# m140_attiny_V5c.net
KiCad netlist of a schematic drawn in EAGLE
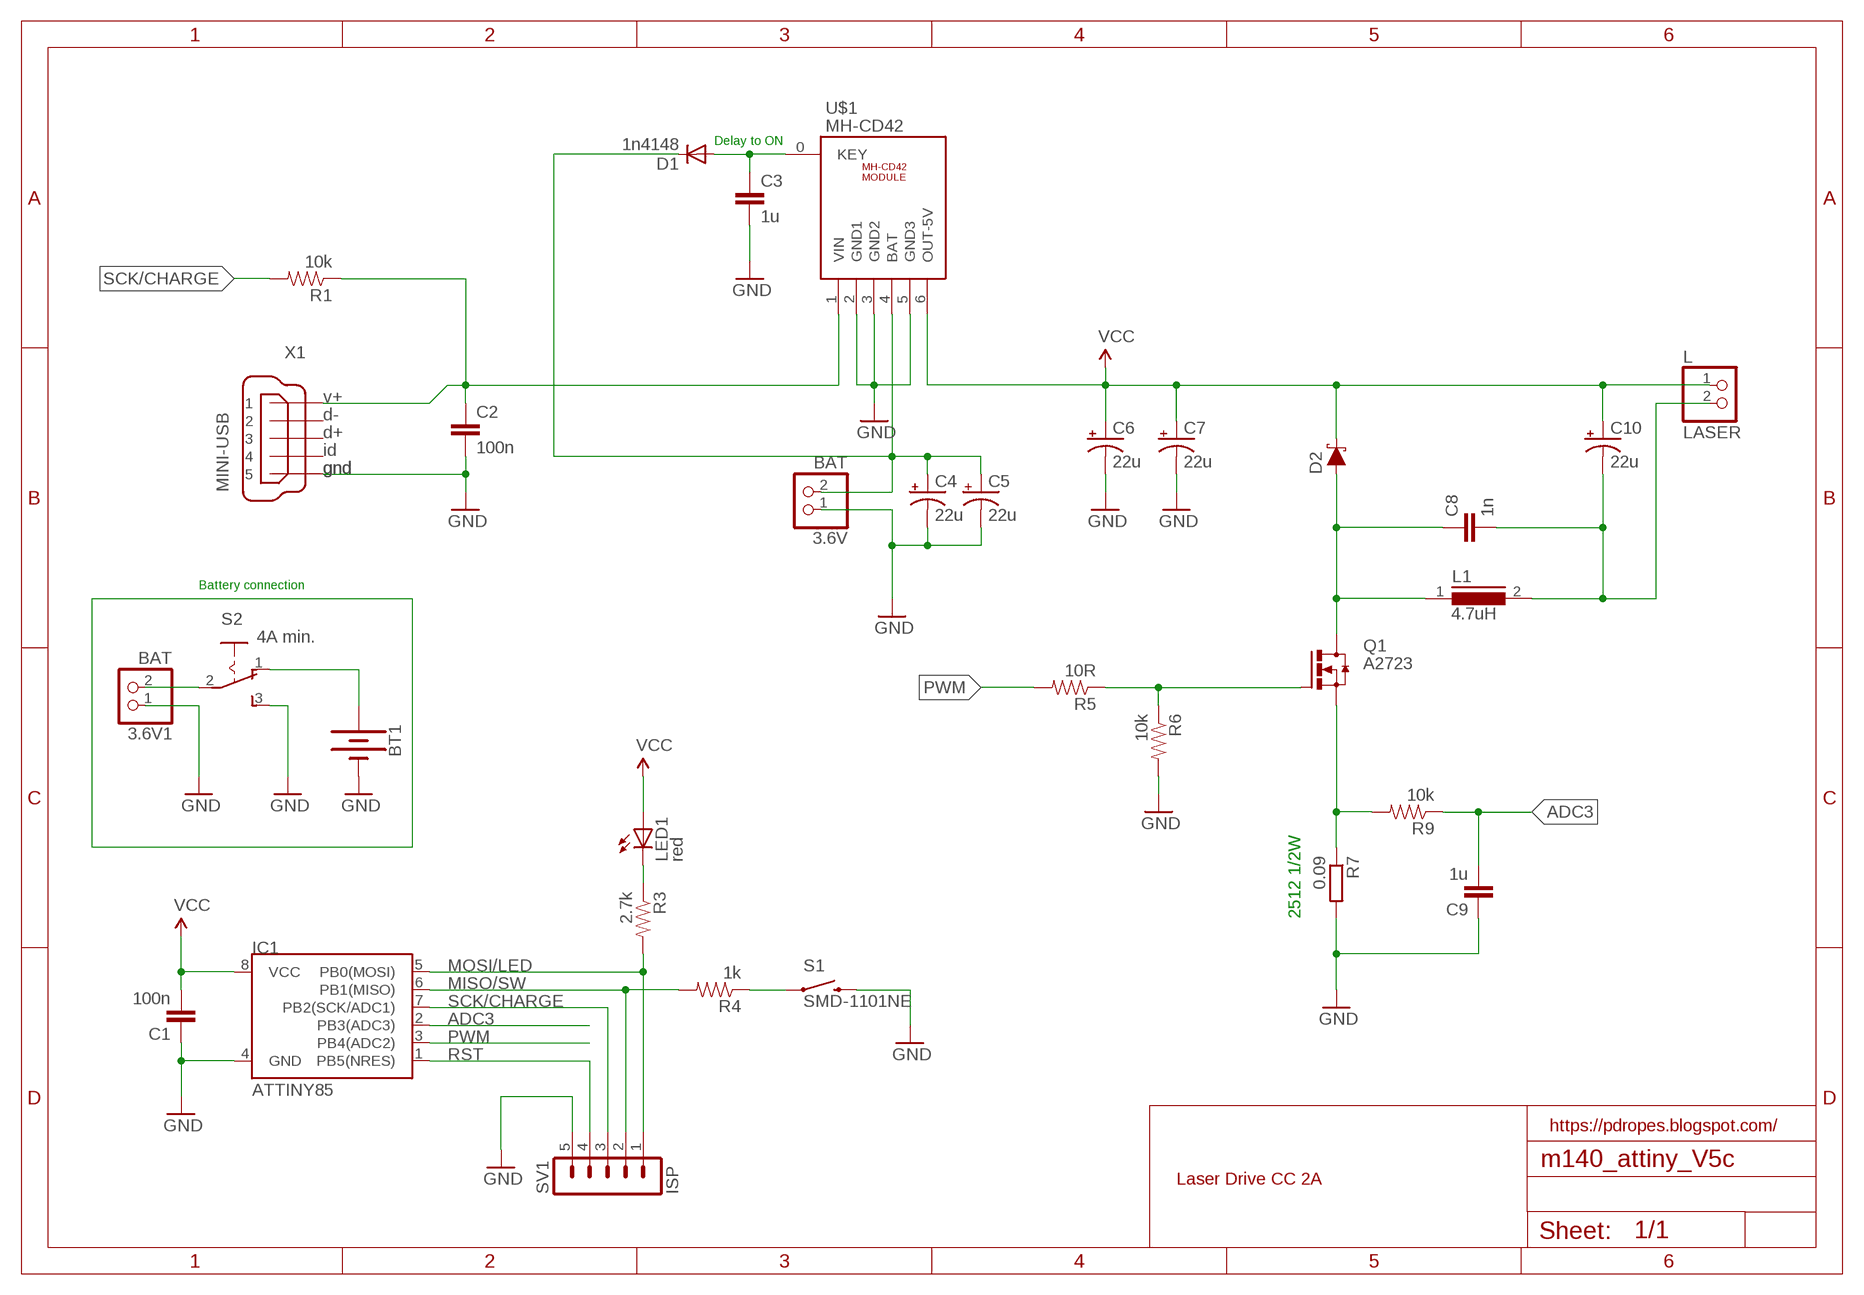
[diagram p0: schematic, sheet 1]

(export (version "E")
  (design (tool "Eeschema 10.0.6"))
  (components
    (comp (ref "3.6V")
      (value "BAT")
      (footprint "eagle-import:1X02")
      (libsource (lib "eagle-import") (part "PINHD-1X2"))
    )
    (comp (ref "3.6V1")
      (value "BAT")
      (footprint "eagle-import:1X02")
      (libsource (lib "eagle-import") (part "PINHD-1X2"))
    )
    (comp (ref "BT1")
      (value "BATTERY-18650")
      (footprint "eagle-import:BATTERY_18650-HOLDER")
      (libsource (lib "eagle-import") (part "BATTERY-18650"))
    )
    (comp (ref "C1")
      (value "100n")
      (footprint "eagle-import:0805")
      (libsource (lib "eagle-import") (part "CAP0805"))
    )
    (comp (ref "C2")
      (value "100n")
      (footprint "eagle-import:0805")
      (libsource (lib "eagle-import") (part "CAP0805"))
    )
    (comp (ref "C3")
      (value "1u")
      (footprint "eagle-import:0805")
      (libsource (lib "eagle-import") (part "CAP0805"))
    )
    (comp (ref "C4")
      (value "22u")
      (footprint "eagle-import:EIA3216-KIT")
      (libsource (lib "eagle-import") (part "CAP_POL1206-KIT"))
    )
    (comp (ref "C5")
      (value "22u")
      (footprint "eagle-import:EIA3216-KIT")
      (libsource (lib "eagle-import") (part "CAP_POL1206-KIT"))
    )
    (comp (ref "C6")
      (value "22u")
      (footprint "eagle-import:EIA3216-KIT")
      (libsource (lib "eagle-import") (part "CAP_POL1206-KIT"))
    )
    (comp (ref "C7")
      (value "22u")
      (footprint "eagle-import:EIA3216-KIT")
      (libsource (lib "eagle-import") (part "CAP_POL1206-KIT"))
    )
    (comp (ref "C8")
      (value "1n")
      (footprint "eagle-import:0805")
      (libsource (lib "eagle-import") (part "CAP0805"))
    )
    (comp (ref "C9")
      (value "1u")
      (footprint "eagle-import:0805")
      (libsource (lib "eagle-import") (part "CAP0805"))
    )
    (comp (ref "C10")
      (value "22u")
      (footprint "eagle-import:EIA3216-KIT")
      (libsource (lib "eagle-import") (part "CAP_POL1206-KIT"))
    )
    (comp (ref "D1")
      (value "1n4148")
      (footprint "eagle-import:MICROMELF-R")
      (libsource (lib "eagle-import") (part "DIODE-MICROMELF-R"))
    )
    (comp (ref "D2")
      (value "3A/40V/500mV")
      (footprint "eagle-import:SMA-DIODE")
      (libsource (lib "eagle-import") (part "DIODE-SCHOTTKY-B340A"))
    )
    (comp (ref "IC1")
      (value "ATTINY85")
      (footprint "eagle-import:SO08-EIAJ")
      (libsource (lib "eagle-import") (part "ATTINY45"))
    )
    (comp (ref "L")
      (value "LASER")
      (footprint "eagle-import:1X02")
      (libsource (lib "eagle-import") (part "PINHD-1X2"))
    )
    (comp (ref "L1")
      (value "4.7uH")
      (footprint "eagle-import:DR74")
      (libsource (lib "eagle-import") (part "DR74"))
    )
    (comp (ref "LED1")
      (value "red")
      (footprint "eagle-import:CHIPLED_0805")
      (libsource (lib "eagle-import") (part "LEDCHIPLED_0805"))
    )
    (comp (ref "Q1")
      (value "A2723")
      (footprint "eagle-import:SOP-ADVANCE")
      (libsource (lib "eagle-import") (part "TPCA8005-H"))
    )
    (comp (ref "R1")
      (value "10k")
      (footprint "eagle-import:0805")
      (libsource (lib "eagle-import") (part "RESISTOR0805-RES"))
    )
    (comp (ref "R3")
      (value "2.7k")
      (footprint "eagle-import:0805")
      (libsource (lib "eagle-import") (part "RESISTOR0805-RES"))
    )
    (comp (ref "R4")
      (value "1k")
      (footprint "eagle-import:0805")
      (libsource (lib "eagle-import") (part "RESISTOR0805-RES"))
    )
    (comp (ref "R5")
      (value "10R")
      (footprint "eagle-import:0805")
      (libsource (lib "eagle-import") (part "RESISTOR0805-RES"))
    )
    (comp (ref "R6")
      (value "10k")
      (footprint "eagle-import:0805")
      (libsource (lib "eagle-import") (part "RESISTOR0805-RES"))
    )
    (comp (ref "R7")
      (value "0.09")
      (footprint "eagle-import:R2512")
      (libsource (lib "eagle-import") (part "R-EU_R2512"))
    )
    (comp (ref "R9")
      (value "10k")
      (footprint "eagle-import:0805")
      (libsource (lib "eagle-import") (part "RESISTOR0805-RES"))
    )
    (comp (ref "S1")
      (value "SMD-1101NE")
      (footprint "eagle-import:TACTILE-SWITCH-1101NE")
      (libsource (lib "eagle-import") (part "SWITCH-MOMENTARY-2-SMD-1101NE"))
    )
    (comp (ref "S2")
      (value "4A min.")
      (footprint "eagle-import:255SB")
      (libsource (lib "eagle-import") (part "255SB"))
    )
    (comp (ref "SV1")
      (value "ISP")
      (footprint "eagle-import:MA05-1")
      (libsource (lib "eagle-import") (part "MA05-1"))
    )
    (comp (ref "U$1")
      (value "MH-CD42")
      (footprint "eagle-import:MH-CD42")
      (libsource (lib "eagle-import") (part "MH-CD42"))
    )
    (comp (ref "X1")
      (value "MINI-USB")
      (footprint "eagle-import:32005-301")
      (libsource (lib "eagle-import") (part "MINI-USB-32005-301"))
    )
  )
  (nets
    (net (code "1") (name "/MISO{slash}SW") (class "Default")
      (node (ref "IC1") (pin "6") (pinfunction "PB1(MISO)_6") (pintype "bidirectional"))
      (node (ref "R4") (pin "2") (pinfunction "2_2") (pintype "passive"))
      (node (ref "SV1") (pin "2") (pinfunction "2_2") (pintype "passive"))
    )
    (net (code "2") (name "/MOSI{slash}LED") (class "Default")
      (node (ref "IC1") (pin "5") (pinfunction "PB0(MOSI)_5") (pintype "bidirectional"))
      (node (ref "R3") (pin "2") (pinfunction "2_2") (pintype "passive"))
      (node (ref "SV1") (pin "1") (pinfunction "1_1") (pintype "passive"))
    )
    (net (code "3") (name "/RST") (class "Default")
      (node (ref "IC1") (pin "1") (pinfunction "PB5(NRES)_1") (pintype "bidirectional"))
      (node (ref "SV1") (pin "4") (pinfunction "4_4") (pintype "passive"))
    )
    (net (code "4") (name "ADC3") (class "Default")
      (node (ref "C9") (pin "2") (pinfunction "2_2") (pintype "passive"))
      (node (ref "IC1") (pin "2") (pinfunction "PB3(ADC3)_2") (pintype "bidirectional"))
      (node (ref "R9") (pin "1") (pinfunction "1_1") (pintype "passive"))
    )
    (net (code "5") (name "GND") (class "Default")
      (node (ref "3.6V") (pin "1") (pinfunction "1_1") (pintype "passive"))
      (node (ref "3.6V1") (pin "1") (pinfunction "1_1") (pintype "passive"))
      (node (ref "BT1") (pin "GND@1") (pinfunction "-_GND@1") (pintype "power_in"))
      (node (ref "C1") (pin "1") (pinfunction "1_1") (pintype "passive"))
      (node (ref "C2") (pin "2") (pinfunction "2_2") (pintype "passive"))
      (node (ref "C3") (pin "2") (pinfunction "2_2") (pintype "passive"))
      (node (ref "C4") (pin "C") (pinfunction "-_C") (pintype "passive"))
      (node (ref "C5") (pin "C") (pinfunction "-_C") (pintype "passive"))
      (node (ref "C6") (pin "C") (pinfunction "-_C") (pintype "passive"))
      (node (ref "C7") (pin "C") (pinfunction "-_C") (pintype "passive"))
      (node (ref "C9") (pin "1") (pinfunction "1_1") (pintype "passive"))
      (node (ref "IC1") (pin "4") (pinfunction "GND_4") (pintype "bidirectional"))
      (node (ref "R6") (pin "2") (pinfunction "2_2") (pintype "passive"))
      (node (ref "R7") (pin "2") (pinfunction "2_2") (pintype "passive"))
      (node (ref "S1") (pin "P$2") (pinfunction "2_P$2") (pintype "passive"))
      (node (ref "S2") (pin "3") (pinfunction "S_3") (pintype "passive"))
      (node (ref "SV1") (pin "5") (pinfunction "5_5") (pintype "passive"))
      (node (ref "U$1") (pin "2") (pinfunction "GND1_2") (pintype "power_in"))
      (node (ref "U$1") (pin "3") (pinfunction "GND2_3") (pintype "power_in"))
      (node (ref "U$1") (pin "5") (pinfunction "GND3_5") (pintype "power_in"))
      (node (ref "X1") (pin "5") (pinfunction "5_5") (pintype "passive"))
    )
    (net (code "6") (name "Net-(BT1-+)") (class "Default")
      (node (ref "BT1") (pin "PWR@1") (pinfunction "+_PWR@1") (pintype "power_in"))
      (node (ref "S2") (pin "1") (pinfunction "O_1") (pintype "passive"))
    )
    (net (code "7") (name "Net-(C4-+)") (class "Default")
      (node (ref "3.6V") (pin "2") (pinfunction "2_2") (pintype "passive"))
      (node (ref "C4") (pin "A") (pinfunction "+_A") (pintype "passive"))
      (node (ref "C5") (pin "A") (pinfunction "+_A") (pintype "passive"))
      (node (ref "D1") (pin "C") (pinfunction "C_C") (pintype "passive"))
      (node (ref "U$1") (pin "4") (pinfunction "BAT_4") (pintype "power_in"))
    )
    (net (code "8") (name "Net-(C8-Pad1)") (class "Default")
      (node (ref "C8") (pin "1") (pinfunction "1_1") (pintype "passive"))
      (node (ref "D2") (pin "A") (pinfunction "A_A") (pintype "passive"))
      (node (ref "L1") (pin "1") (pinfunction "1_1") (pintype "passive"))
      (node (ref "Q1") (pin "5") (pinfunction "D_5") (pintype "passive"))
      (node (ref "Q1") (pin "6") (pinfunction "D_6") (pintype "passive"))
      (node (ref "Q1") (pin "7") (pinfunction "D_7") (pintype "passive"))
      (node (ref "Q1") (pin "8") (pinfunction "D_8") (pintype "passive"))
      (node (ref "Q1") (pin "TH") (pinfunction "D_TH") (pintype "passive"))
    )
    (net (code "9") (name "Net-(C10--)") (class "Default")
      (node (ref "C10") (pin "C") (pinfunction "-_C") (pintype "passive"))
      (node (ref "C8") (pin "2") (pinfunction "2_2") (pintype "passive"))
      (node (ref "L") (pin "2") (pinfunction "2_2") (pintype "passive"))
      (node (ref "L1") (pin "2") (pinfunction "2_2") (pintype "passive"))
    )
    (net (code "10") (name "Net-(LED1-PadC)") (class "Default")
      (node (ref "LED1") (pin "C") (pinfunction "C_C") (pintype "passive"))
      (node (ref "R3") (pin "1") (pinfunction "1_1") (pintype "passive"))
    )
    (net (code "11") (name "Net-(Q1-G)") (class "Default")
      (node (ref "Q1") (pin "4") (pinfunction "G_4") (pintype "passive"))
      (node (ref "R5") (pin "1") (pinfunction "1_1") (pintype "passive"))
      (node (ref "R6") (pin "1") (pinfunction "1_1") (pintype "passive"))
    )
    (net (code "12") (name "Net-(Q1-S-Pad1)") (class "Default")
      (node (ref "Q1") (pin "1") (pinfunction "S_1") (pintype "passive"))
      (node (ref "Q1") (pin "2") (pinfunction "S_2") (pintype "passive"))
      (node (ref "Q1") (pin "3") (pinfunction "S_3") (pintype "passive"))
      (node (ref "R7") (pin "1") (pinfunction "1_1") (pintype "passive"))
      (node (ref "R9") (pin "2") (pinfunction "2_2") (pintype "passive"))
    )
    (net (code "13") (name "Net-(S1-1)") (class "Default")
      (node (ref "R4") (pin "1") (pinfunction "1_1") (pintype "passive"))
      (node (ref "S1") (pin "P$1") (pinfunction "1_P$1") (pintype "passive"))
    )
    (net (code "14") (name "Net-(S2-P)") (class "Default")
      (node (ref "3.6V1") (pin "2") (pinfunction "2_2") (pintype "passive"))
      (node (ref "S2") (pin "2") (pinfunction "P_2") (pintype "passive"))
    )
    (net (code "15") (name "Net-(U$1-KEY)") (class "Default")
      (node (ref "C3") (pin "1") (pinfunction "1_1") (pintype "passive"))
      (node (ref "D1") (pin "A") (pinfunction "A_A") (pintype "passive"))
      (node (ref "U$1") (pin "0") (pinfunction "KEY_0") (pintype "input"))
    )
    (net (code "16") (name "Net-(U$1-VIN)") (class "Default")
      (node (ref "C2") (pin "1") (pinfunction "1_1") (pintype "passive"))
      (node (ref "R1") (pin "1") (pinfunction "1_1") (pintype "passive"))
      (node (ref "U$1") (pin "1") (pinfunction "VIN_1") (pintype "power_in"))
      (node (ref "X1") (pin "1") (pinfunction "1_1") (pintype "passive"))
    )
    (net (code "17") (name "PWM") (class "Default")
      (node (ref "IC1") (pin "3") (pinfunction "PB4(ADC2)_3") (pintype "bidirectional"))
      (node (ref "R5") (pin "2") (pinfunction "2_2") (pintype "passive"))
    )
    (net (code "18") (name "SCK{slash}CHARGE") (class "Default")
      (node (ref "IC1") (pin "7") (pinfunction "PB2(SCK/ADC1)_7") (pintype "bidirectional"))
      (node (ref "R1") (pin "2") (pinfunction "2_2") (pintype "passive"))
      (node (ref "SV1") (pin "3") (pinfunction "3_3") (pintype "passive"))
    )
    (net (code "19") (name "VCC") (class "Default")
      (node (ref "C1") (pin "2") (pinfunction "2_2") (pintype "passive"))
      (node (ref "C10") (pin "A") (pinfunction "+_A") (pintype "passive"))
      (node (ref "C6") (pin "A") (pinfunction "+_A") (pintype "passive"))
      (node (ref "C7") (pin "A") (pinfunction "+_A") (pintype "passive"))
      (node (ref "D2") (pin "C") (pinfunction "C_C") (pintype "passive"))
      (node (ref "IC1") (pin "8") (pinfunction "VCC_8") (pintype "bidirectional"))
      (node (ref "L") (pin "1") (pinfunction "1_1") (pintype "passive"))
      (node (ref "LED1") (pin "A") (pinfunction "A_A") (pintype "passive"))
      (node (ref "U$1") (pin "6") (pinfunction "OUT-5V_6") (pintype "passive"))
    )
    (net (code "20") (name "unconnected-(X1-Pad2)") (class "Default")
      (node (ref "X1") (pin "2") (pinfunction "2_2") (pintype "passive"))
    )
    (net (code "21") (name "unconnected-(X1-Pad3)") (class "Default")
      (node (ref "X1") (pin "3") (pinfunction "3_3") (pintype "passive"))
    )
    (net (code "22") (name "unconnected-(X1-Pad4)") (class "Default")
      (node (ref "X1") (pin "4") (pinfunction "4_4") (pintype "passive"))
    )
  )
)
